# DDR4_SODIMM1.net
KiCad netlist of a schematic drawn in Altium Designer
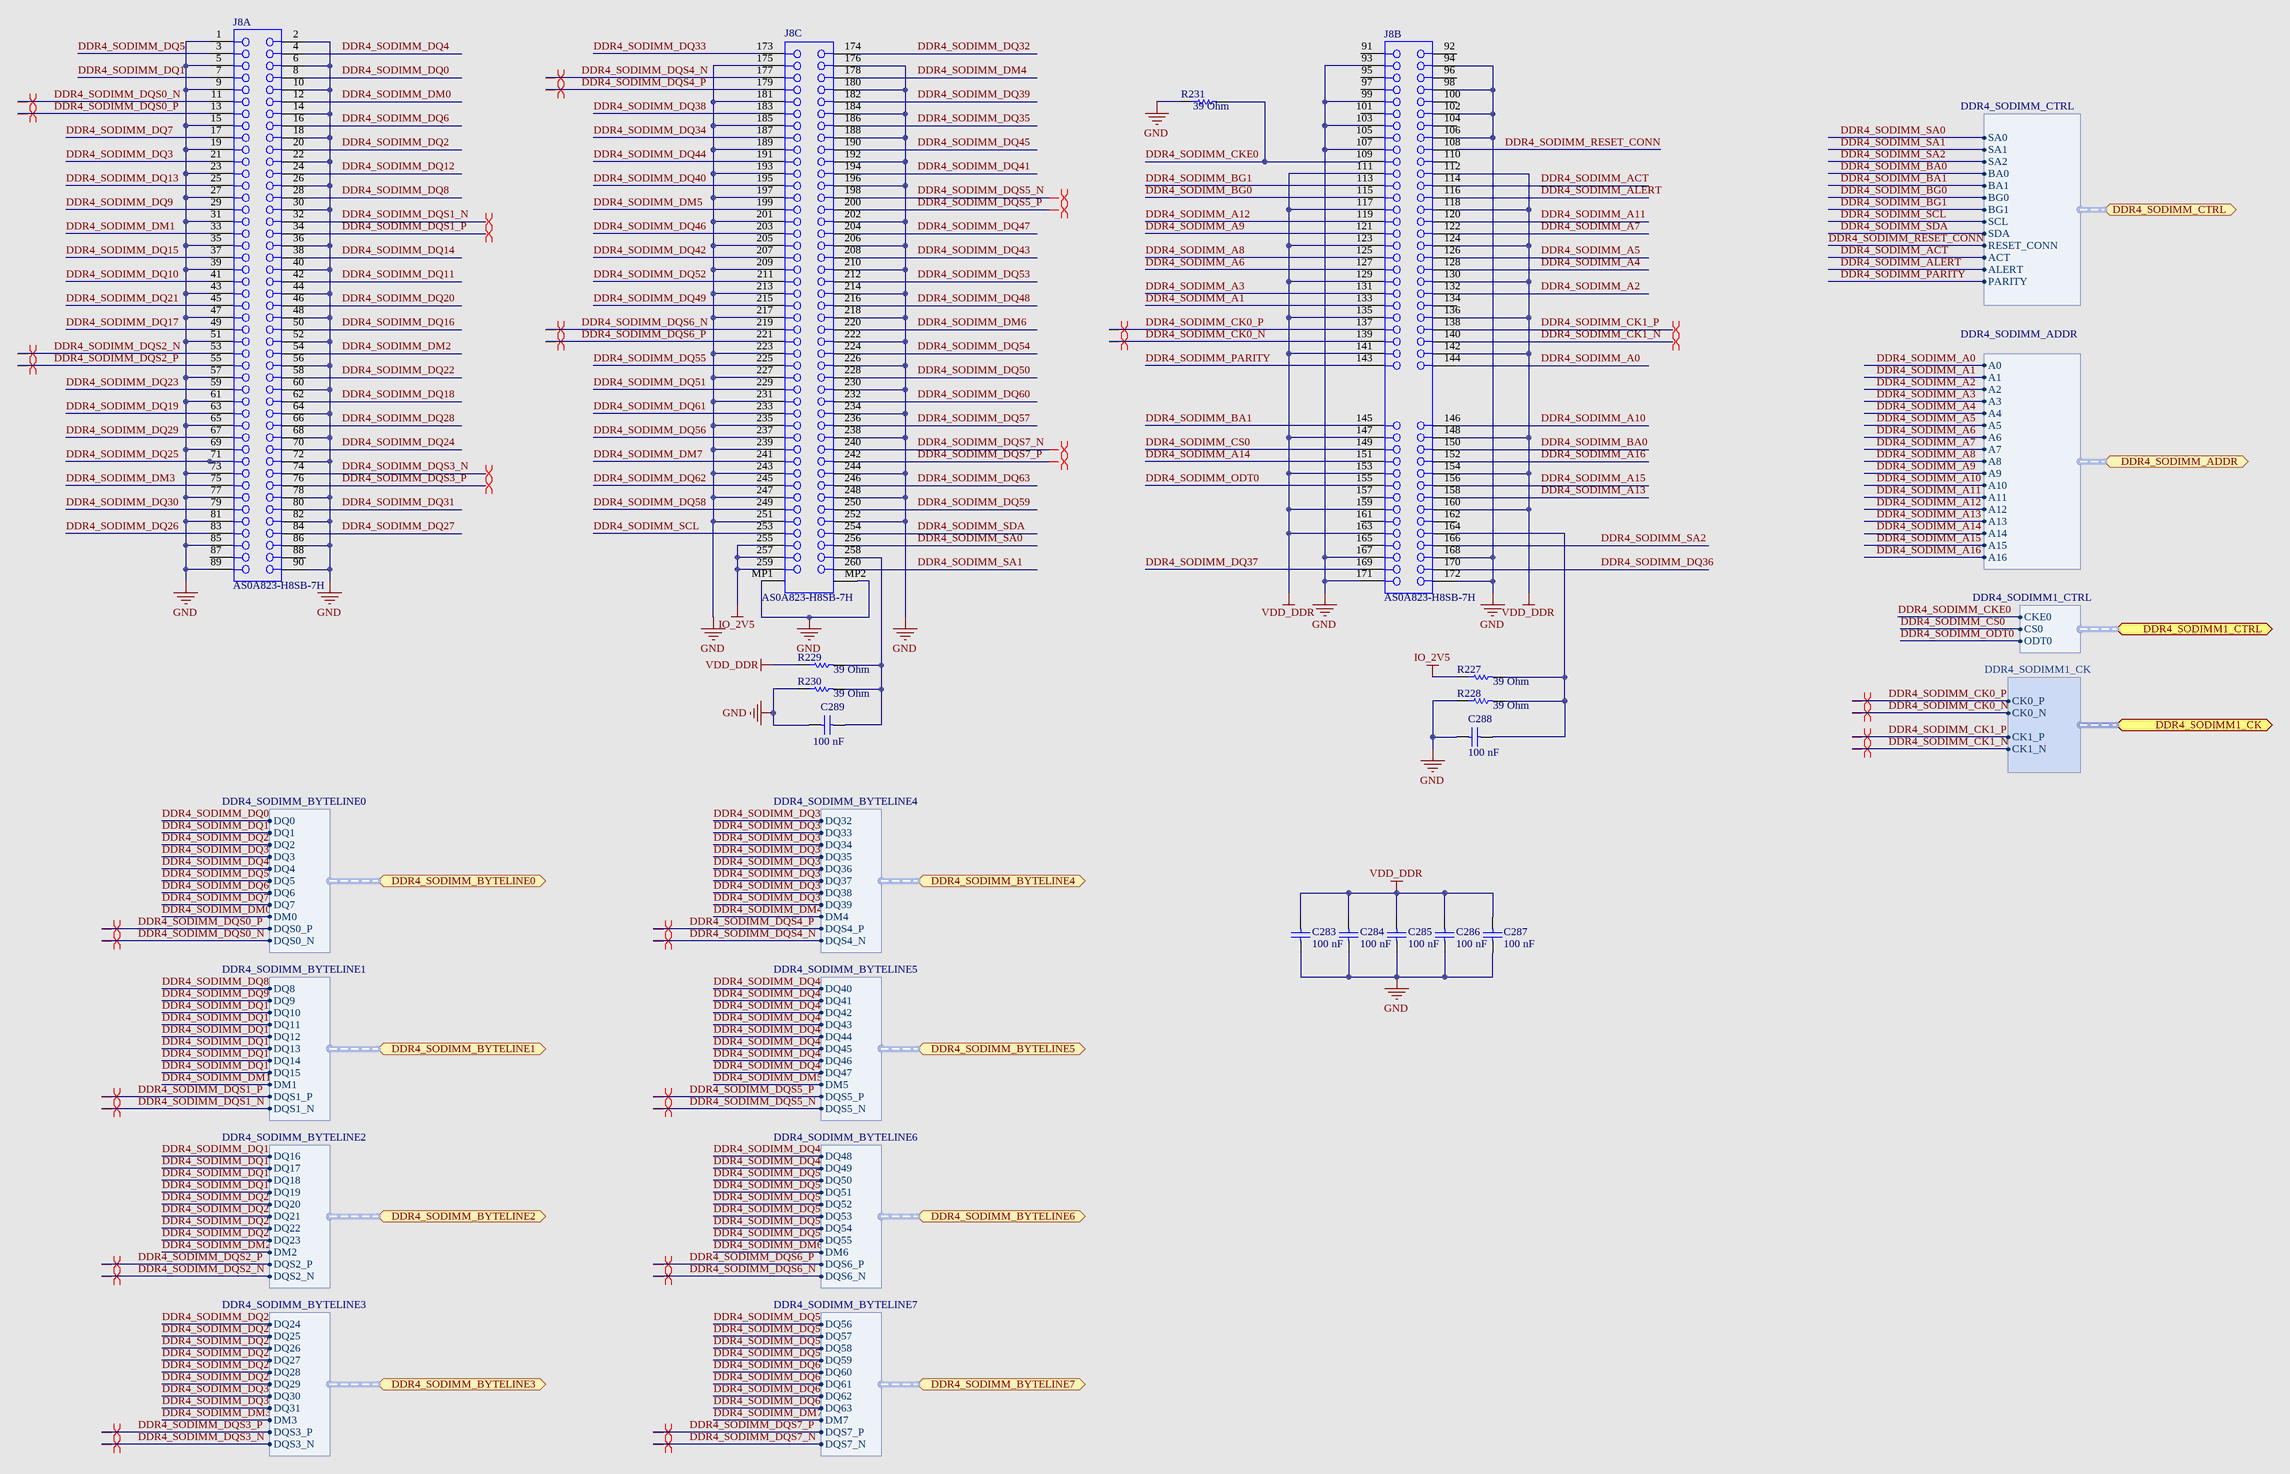
[diagram p0: DDR4_SODIMM1.SchDoc]

(export (version "E")
  (design (tool "Eeschema 10.0.6"))
  (components
    (comp (ref "C283")
      (value "C1005X7R1E104M")
      (footprint "CAPC1005X55X10LL05")
      (description "Chip Capacitor, 0.1 uF, +/- 20%, 25 V, -55 to 125 degC, 0402 (1005 Metric), RoHS, Tape and Reel")
      (fields (field (name "TOLERANCE") "20%") (field (name "CAPACITANCE") "100 nF"))
      (libsource (lib "Altium Content Vault") (part "CAP-NP-2"))
    )
    (comp (ref "C284")
      (value "C1005X7R1E104M")
      (footprint "CAPC1005X55X10LL05")
      (description "Chip Capacitor, 0.1 uF, +/- 20%, 25 V, -55 to 125 degC, 0402 (1005 Metric), RoHS, Tape and Reel")
      (fields (field (name "TOLERANCE") "20%") (field (name "CAPACITANCE") "100 nF"))
      (libsource (lib "Altium Content Vault") (part "CAP-NP-2"))
    )
    (comp (ref "C285")
      (value "C1005X7R1E104M")
      (footprint "CAPC1005X55X10LL05")
      (description "Chip Capacitor, 0.1 uF, +/- 20%, 25 V, -55 to 125 degC, 0402 (1005 Metric), RoHS, Tape and Reel")
      (fields (field (name "TOLERANCE") "20%") (field (name "CAPACITANCE") "100 nF"))
      (libsource (lib "Altium Content Vault") (part "CAP-NP-2"))
    )
    (comp (ref "C286")
      (value "C1005X7R1E104M")
      (footprint "CAPC1005X55X10LL05")
      (description "Chip Capacitor, 0.1 uF, +/- 20%, 25 V, -55 to 125 degC, 0402 (1005 Metric), RoHS, Tape and Reel")
      (fields (field (name "TOLERANCE") "20%") (field (name "CAPACITANCE") "100 nF"))
      (libsource (lib "Altium Content Vault") (part "CAP-NP-2"))
    )
    (comp (ref "C287")
      (value "C1005X7R1E104M")
      (footprint "CAPC1005X55X10LL05")
      (description "Chip Capacitor, 0.1 uF, +/- 20%, 25 V, -55 to 125 degC, 0402 (1005 Metric), RoHS, Tape and Reel")
      (fields (field (name "TOLERANCE") "20%") (field (name "CAPACITANCE") "100 nF"))
      (libsource (lib "Altium Content Vault") (part "CAP-NP-2"))
    )
    (comp (ref "C288")
      (value "C1005X7R1E104M")
      (footprint "CAPC1005X55X10LL05")
      (description "Chip Capacitor, 0.1 uF, +/- 20%, 25 V, -55 to 125 degC, 0402 (1005 Metric), RoHS, Tape and Reel")
      (fields (field (name "TOLERANCE") "20%") (field (name "CAPACITANCE") "100 nF"))
      (libsource (lib "Altium Content Vault") (part "CAP-NP-2"))
    )
    (comp (ref "C289")
      (value "C1005X7R1E104M")
      (footprint "CAPC1005X55X10LL05")
      (description "Chip Capacitor, 0.1 uF, +/- 20%, 25 V, -55 to 125 degC, 0402 (1005 Metric), RoHS, Tape and Reel")
      (fields (field (name "TOLERANCE") "20%") (field (name "CAPACITANCE") "100 nF"))
      (libsource (lib "Altium Content Vault") (part "CAP-NP-2"))
    )
    (comp (ref "J8")
      (value "AS0A823-H8SB-7H")
      (footprint "FOXC-AS0A823-H8SB-7H_V")
      (libsource (lib "Altium Content Vault") (part "CN-2S-2F-R260"))
    )
    (comp (ref "R227")
      (value "RC0402JR-0739RL")
      (footprint "RESC1005X40X25NL5T10")
      (description "Chip Resistor, 39 Ohm, +/- 5%, 0.063 W, -55 to 155 degC, 0402 (1005 Metric), RoHS, Tape and Reel")
      (fields (field (name "TOLERANCE") "5%") (field (name "RESISTANCE") "39 Ohm"))
      (libsource (lib "Altium Content Vault") (part "CMP-2002-07994-2"))
    )
    (comp (ref "R228")
      (value "RC0402JR-0739RL")
      (footprint "RESC1005X40X25NL5T10")
      (description "Chip Resistor, 39 Ohm, +/- 5%, 0.063 W, -55 to 155 degC, 0402 (1005 Metric), RoHS, Tape and Reel")
      (fields (field (name "TOLERANCE") "5%") (field (name "RESISTANCE") "39 Ohm"))
      (libsource (lib "Altium Content Vault") (part "CMP-2002-07994-2"))
    )
    (comp (ref "R229")
      (value "RC0402JR-0739RL")
      (footprint "RESC1005X40X25NL5T10")
      (description "Chip Resistor, 39 Ohm, +/- 5%, 0.063 W, -55 to 155 degC, 0402 (1005 Metric), RoHS, Tape and Reel")
      (fields (field (name "TOLERANCE") "5%") (field (name "RESISTANCE") "39 Ohm"))
      (libsource (lib "Altium Content Vault") (part "CMP-2002-07994-2"))
    )
    (comp (ref "R230")
      (value "RC0402JR-0739RL")
      (footprint "RESC1005X40X25NL5T10")
      (description "Chip Resistor, 39 Ohm, +/- 5%, 0.063 W, -55 to 155 degC, 0402 (1005 Metric), RoHS, Tape and Reel")
      (fields (field (name "TOLERANCE") "5%") (field (name "RESISTANCE") "39 Ohm"))
      (libsource (lib "Altium Content Vault") (part "CMP-2002-07994-2"))
    )
    (comp (ref "R231")
      (value "RC0402JR-0739RL")
      (footprint "RESC1005X40X25NL5T10")
      (description "Chip Resistor, 39 Ohm, +/- 5%, 0.063 W, -55 to 155 degC, 0402 (1005 Metric), RoHS, Tape and Reel")
      (fields (field (name "TOLERANCE") "5%") (field (name "RESISTANCE") "39 Ohm"))
      (libsource (lib "Altium Content Vault") (part "CMP-2002-07994-2"))
    )
  )
  (nets
    (net (code "13") (name "/DDR4_SODIMM_A0") (class "Default")
      (node (ref "J8") (pin "144") (pinfunction "144_144") (pintype "passive"))
    )
    (net (code "14") (name "/DDR4_SODIMM_A1") (class "Default")
      (node (ref "J8") (pin "133") (pinfunction "133_133") (pintype "passive"))
    )
    (net (code "15") (name "/DDR4_SODIMM_A2") (class "Default")
      (node (ref "J8") (pin "132") (pinfunction "132_132") (pintype "passive"))
    )
    (net (code "16") (name "/DDR4_SODIMM_A3") (class "Default")
      (node (ref "J8") (pin "131") (pinfunction "131_131") (pintype "passive"))
    )
    (net (code "17") (name "/DDR4_SODIMM_A4") (class "Default")
      (node (ref "J8") (pin "128") (pinfunction "128_128") (pintype "passive"))
    )
    (net (code "18") (name "/DDR4_SODIMM_A5") (class "Default")
      (node (ref "J8") (pin "126") (pinfunction "126_126") (pintype "passive"))
    )
    (net (code "19") (name "/DDR4_SODIMM_A6") (class "Default")
      (node (ref "J8") (pin "127") (pinfunction "127_127") (pintype "passive"))
    )
    (net (code "20") (name "/DDR4_SODIMM_A7") (class "Default")
      (node (ref "J8") (pin "122") (pinfunction "122_122") (pintype "passive"))
    )
    (net (code "21") (name "/DDR4_SODIMM_A8") (class "Default")
      (node (ref "J8") (pin "125") (pinfunction "125_125") (pintype "passive"))
    )
    (net (code "22") (name "/DDR4_SODIMM_A9") (class "Default")
      (node (ref "J8") (pin "121") (pinfunction "121_121") (pintype "passive"))
    )
    (net (code "23") (name "/DDR4_SODIMM_A10") (class "Default")
      (node (ref "J8") (pin "146") (pinfunction "146_146") (pintype "passive"))
    )
    (net (code "24") (name "/DDR4_SODIMM_A11") (class "Default")
      (node (ref "J8") (pin "120") (pinfunction "120_120") (pintype "passive"))
    )
    (net (code "25") (name "/DDR4_SODIMM_A12") (class "Default")
      (node (ref "J8") (pin "119") (pinfunction "119_119") (pintype "passive"))
    )
    (net (code "26") (name "/DDR4_SODIMM_A13") (class "Default")
      (node (ref "J8") (pin "158") (pinfunction "158_158") (pintype "passive"))
    )
    (net (code "27") (name "/DDR4_SODIMM_A14") (class "Default")
      (node (ref "J8") (pin "151") (pinfunction "151_151") (pintype "passive"))
    )
    (net (code "28") (name "/DDR4_SODIMM_A15") (class "Default")
      (node (ref "J8") (pin "156") (pinfunction "156_156") (pintype "passive"))
    )
    (net (code "29") (name "/DDR4_SODIMM_A16") (class "Default")
      (node (ref "J8") (pin "152") (pinfunction "152_152") (pintype "passive"))
    )
    (net (code "30") (name "/DDR4_SODIMM_ACT") (class "Default")
      (node (ref "J8") (pin "114") (pinfunction "114_114") (pintype "passive"))
    )
    (net (code "31") (name "/DDR4_SODIMM_ALERT") (class "Default")
      (node (ref "J8") (pin "116") (pinfunction "116_116") (pintype "passive"))
    )
    (net (code "32") (name "/DDR4_SODIMM_BA0") (class "Default")
      (node (ref "J8") (pin "150") (pinfunction "150_150") (pintype "passive"))
    )
    (net (code "33") (name "/DDR4_SODIMM_BA1") (class "Default")
      (node (ref "J8") (pin "145") (pinfunction "145_145") (pintype "passive"))
    )
    (net (code "34") (name "/DDR4_SODIMM_BG0") (class "Default")
      (node (ref "J8") (pin "115") (pinfunction "115_115") (pintype "passive"))
    )
    (net (code "35") (name "/DDR4_SODIMM_BG1") (class "Default")
      (node (ref "J8") (pin "113") (pinfunction "113_113") (pintype "passive"))
    )
    (net (code "36") (name "/DDR4_SODIMM_CK0_N") (class "Default")
      (node (ref "J8") (pin "139") (pinfunction "139_139") (pintype "passive"))
    )
    (net (code "37") (name "/DDR4_SODIMM_CK0_P") (class "Default")
      (node (ref "J8") (pin "137") (pinfunction "137_137") (pintype "passive"))
    )
    (net (code "38") (name "/DDR4_SODIMM_CK1_N") (class "Default")
      (node (ref "J8") (pin "140") (pinfunction "140_140") (pintype "passive"))
    )
    (net (code "39") (name "/DDR4_SODIMM_CK1_P") (class "Default")
      (node (ref "J8") (pin "138") (pinfunction "138_138") (pintype "passive"))
    )
    (net (code "40") (name "/DDR4_SODIMM_CKE0") (class "Default")
      (node (ref "J8") (pin "109") (pinfunction "109_109") (pintype "passive"))
      (node (ref "R231") (pin "2") (pinfunction "2_2") (pintype "passive"))
    )
    (net (code "41") (name "/DDR4_SODIMM_CS0") (class "Default")
      (node (ref "J8") (pin "149") (pinfunction "149_149") (pintype "passive"))
    )
    (net (code "42") (name "/DDR4_SODIMM_DM0") (class "Default")
      (node (ref "J8") (pin "12") (pinfunction "12_12") (pintype "passive"))
    )
    (net (code "43") (name "/DDR4_SODIMM_DM1") (class "Default")
      (node (ref "J8") (pin "33") (pinfunction "33_33") (pintype "passive"))
    )
    (net (code "44") (name "/DDR4_SODIMM_DM2") (class "Default")
      (node (ref "J8") (pin "54") (pinfunction "54_54") (pintype "passive"))
    )
    (net (code "45") (name "/DDR4_SODIMM_DM3") (class "Default")
      (node (ref "J8") (pin "75") (pinfunction "75_75") (pintype "passive"))
    )
    (net (code "46") (name "/DDR4_SODIMM_DM4") (class "Default")
      (node (ref "J8") (pin "178") (pinfunction "178_178") (pintype "passive"))
    )
    (net (code "47") (name "/DDR4_SODIMM_DM5") (class "Default")
      (node (ref "J8") (pin "199") (pinfunction "199_199") (pintype "passive"))
    )
    (net (code "48") (name "/DDR4_SODIMM_DM6") (class "Default")
      (node (ref "J8") (pin "220") (pinfunction "220_220") (pintype "passive"))
    )
    (net (code "49") (name "/DDR4_SODIMM_DM7") (class "Default")
      (node (ref "J8") (pin "241") (pinfunction "241_241") (pintype "passive"))
    )
    (net (code "50") (name "/DDR4_SODIMM_DQ0") (class "Default")
      (node (ref "J8") (pin "8") (pinfunction "8_8") (pintype "passive"))
    )
    (net (code "51") (name "/DDR4_SODIMM_DQ1") (class "Default")
      (node (ref "J8") (pin "7") (pinfunction "7_7") (pintype "passive"))
    )
    (net (code "52") (name "/DDR4_SODIMM_DQ2") (class "Default")
      (node (ref "J8") (pin "20") (pinfunction "20_20") (pintype "passive"))
    )
    (net (code "53") (name "/DDR4_SODIMM_DQ3") (class "Default")
      (node (ref "J8") (pin "21") (pinfunction "21_21") (pintype "passive"))
    )
    (net (code "54") (name "/DDR4_SODIMM_DQ4") (class "Default")
      (node (ref "J8") (pin "4") (pinfunction "4_4") (pintype "passive"))
    )
    (net (code "55") (name "/DDR4_SODIMM_DQ5") (class "Default")
      (node (ref "J8") (pin "3") (pinfunction "3_3") (pintype "passive"))
    )
    (net (code "56") (name "/DDR4_SODIMM_DQ6") (class "Default")
      (node (ref "J8") (pin "16") (pinfunction "16_16") (pintype "passive"))
    )
    (net (code "57") (name "/DDR4_SODIMM_DQ7") (class "Default")
      (node (ref "J8") (pin "17") (pinfunction "17_17") (pintype "passive"))
    )
    (net (code "58") (name "/DDR4_SODIMM_DQ8") (class "Default")
      (node (ref "J8") (pin "28") (pinfunction "28_28") (pintype "passive"))
    )
    (net (code "59") (name "/DDR4_SODIMM_DQ9") (class "Default")
      (node (ref "J8") (pin "29") (pinfunction "29_29") (pintype "passive"))
    )
    (net (code "60") (name "/DDR4_SODIMM_DQ10") (class "Default")
      (node (ref "J8") (pin "41") (pinfunction "41_41") (pintype "passive"))
    )
    (net (code "61") (name "/DDR4_SODIMM_DQ11") (class "Default")
      (node (ref "J8") (pin "42") (pinfunction "42_42") (pintype "passive"))
    )
    (net (code "62") (name "/DDR4_SODIMM_DQ12") (class "Default")
      (node (ref "J8") (pin "24") (pinfunction "24_24") (pintype "passive"))
    )
    (net (code "63") (name "/DDR4_SODIMM_DQ13") (class "Default")
      (node (ref "J8") (pin "25") (pinfunction "25_25") (pintype "passive"))
    )
    (net (code "64") (name "/DDR4_SODIMM_DQ14") (class "Default")
      (node (ref "J8") (pin "38") (pinfunction "38_38") (pintype "passive"))
    )
    (net (code "65") (name "/DDR4_SODIMM_DQ15") (class "Default")
      (node (ref "J8") (pin "37") (pinfunction "37_37") (pintype "passive"))
    )
    (net (code "66") (name "/DDR4_SODIMM_DQ16") (class "Default")
      (node (ref "J8") (pin "50") (pinfunction "50_50") (pintype "passive"))
    )
    (net (code "67") (name "/DDR4_SODIMM_DQ17") (class "Default")
      (node (ref "J8") (pin "49") (pinfunction "49_49") (pintype "passive"))
    )
    (net (code "68") (name "/DDR4_SODIMM_DQ18") (class "Default")
      (node (ref "J8") (pin "62") (pinfunction "62_62") (pintype "passive"))
    )
    (net (code "69") (name "/DDR4_SODIMM_DQ19") (class "Default")
      (node (ref "J8") (pin "63") (pinfunction "63_63") (pintype "passive"))
    )
    (net (code "70") (name "/DDR4_SODIMM_DQ20") (class "Default")
      (node (ref "J8") (pin "46") (pinfunction "46_46") (pintype "passive"))
    )
    (net (code "71") (name "/DDR4_SODIMM_DQ21") (class "Default")
      (node (ref "J8") (pin "45") (pinfunction "45_45") (pintype "passive"))
    )
    (net (code "72") (name "/DDR4_SODIMM_DQ22") (class "Default")
      (node (ref "J8") (pin "58") (pinfunction "58_58") (pintype "passive"))
    )
    (net (code "73") (name "/DDR4_SODIMM_DQ23") (class "Default")
      (node (ref "J8") (pin "59") (pinfunction "59_59") (pintype "passive"))
    )
    (net (code "74") (name "/DDR4_SODIMM_DQ24") (class "Default")
      (node (ref "J8") (pin "70") (pinfunction "70_70") (pintype "passive"))
    )
    (net (code "75") (name "/DDR4_SODIMM_DQ25") (class "Default")
      (node (ref "J8") (pin "71") (pinfunction "71_71") (pintype "passive"))
    )
    (net (code "76") (name "/DDR4_SODIMM_DQ26") (class "Default")
      (node (ref "J8") (pin "83") (pinfunction "83_83") (pintype "passive"))
    )
    (net (code "77") (name "/DDR4_SODIMM_DQ27") (class "Default")
      (node (ref "J8") (pin "84") (pinfunction "84_84") (pintype "passive"))
    )
    (net (code "78") (name "/DDR4_SODIMM_DQ28") (class "Default")
      (node (ref "J8") (pin "66") (pinfunction "66_66") (pintype "passive"))
    )
    (net (code "79") (name "/DDR4_SODIMM_DQ29") (class "Default")
      (node (ref "J8") (pin "67") (pinfunction "67_67") (pintype "passive"))
    )
    (net (code "80") (name "/DDR4_SODIMM_DQ30") (class "Default")
      (node (ref "J8") (pin "79") (pinfunction "79_79") (pintype "passive"))
    )
    (net (code "81") (name "/DDR4_SODIMM_DQ31") (class "Default")
      (node (ref "J8") (pin "80") (pinfunction "80_80") (pintype "passive"))
    )
    (net (code "82") (name "/DDR4_SODIMM_DQ32") (class "Default")
      (node (ref "J8") (pin "174") (pinfunction "174_174") (pintype "passive"))
    )
    (net (code "83") (name "/DDR4_SODIMM_DQ33") (class "Default")
      (node (ref "J8") (pin "173") (pinfunction "173_173") (pintype "passive"))
    )
    (net (code "84") (name "/DDR4_SODIMM_DQ34") (class "Default")
      (node (ref "J8") (pin "187") (pinfunction "187_187") (pintype "passive"))
    )
    (net (code "85") (name "/DDR4_SODIMM_DQ35") (class "Default")
      (node (ref "J8") (pin "186") (pinfunction "186_186") (pintype "passive"))
    )
    (net (code "86") (name "/DDR4_SODIMM_DQ36") (class "Default")
      (node (ref "J8") (pin "170") (pinfunction "170_170") (pintype "passive"))
    )
    (net (code "87") (name "/DDR4_SODIMM_DQ37") (class "Default")
      (node (ref "J8") (pin "169") (pinfunction "169_169") (pintype "passive"))
    )
    (net (code "88") (name "/DDR4_SODIMM_DQ38") (class "Default")
      (node (ref "J8") (pin "183") (pinfunction "183_183") (pintype "passive"))
    )
    (net (code "89") (name "/DDR4_SODIMM_DQ39") (class "Default")
      (node (ref "J8") (pin "182") (pinfunction "182_182") (pintype "passive"))
    )
    (net (code "90") (name "/DDR4_SODIMM_DQ40") (class "Default")
      (node (ref "J8") (pin "195") (pinfunction "195_195") (pintype "passive"))
    )
    (net (code "91") (name "/DDR4_SODIMM_DQ41") (class "Default")
      (node (ref "J8") (pin "194") (pinfunction "194_194") (pintype "passive"))
    )
    (net (code "92") (name "/DDR4_SODIMM_DQ42") (class "Default")
      (node (ref "J8") (pin "207") (pinfunction "207_207") (pintype "passive"))
    )
    (net (code "93") (name "/DDR4_SODIMM_DQ43") (class "Default")
      (node (ref "J8") (pin "208") (pinfunction "208_208") (pintype "passive"))
    )
    (net (code "94") (name "/DDR4_SODIMM_DQ44") (class "Default")
      (node (ref "J8") (pin "191") (pinfunction "191_191") (pintype "passive"))
    )
    (net (code "95") (name "/DDR4_SODIMM_DQ45") (class "Default")
      (node (ref "J8") (pin "190") (pinfunction "190_190") (pintype "passive"))
    )
    (net (code "96") (name "/DDR4_SODIMM_DQ46") (class "Default")
      (node (ref "J8") (pin "203") (pinfunction "203_203") (pintype "passive"))
    )
    (net (code "97") (name "/DDR4_SODIMM_DQ47") (class "Default")
      (node (ref "J8") (pin "204") (pinfunction "204_204") (pintype "passive"))
    )
    (net (code "98") (name "/DDR4_SODIMM_DQ48") (class "Default")
      (node (ref "J8") (pin "216") (pinfunction "216_216") (pintype "passive"))
    )
    (net (code "99") (name "/DDR4_SODIMM_DQ49") (class "Default")
      (node (ref "J8") (pin "215") (pinfunction "215_215") (pintype "passive"))
    )
    (net (code "100") (name "/DDR4_SODIMM_DQ50") (class "Default")
      (node (ref "J8") (pin "228") (pinfunction "228_228") (pintype "passive"))
    )
    (net (code "101") (name "/DDR4_SODIMM_DQ51") (class "Default")
      (node (ref "J8") (pin "229") (pinfunction "229_229") (pintype "passive"))
    )
    (net (code "102") (name "/DDR4_SODIMM_DQ52") (class "Default")
      (node (ref "J8") (pin "211") (pinfunction "211_211") (pintype "passive"))
    )
    (net (code "103") (name "/DDR4_SODIMM_DQ53") (class "Default")
      (node (ref "J8") (pin "212") (pinfunction "212_212") (pintype "passive"))
    )
    (net (code "104") (name "/DDR4_SODIMM_DQ54") (class "Default")
      (node (ref "J8") (pin "224") (pinfunction "224_224") (pintype "passive"))
    )
    (net (code "105") (name "/DDR4_SODIMM_DQ55") (class "Default")
      (node (ref "J8") (pin "225") (pinfunction "225_225") (pintype "passive"))
    )
    (net (code "106") (name "/DDR4_SODIMM_DQ56") (class "Default")
      (node (ref "J8") (pin "237") (pinfunction "237_237") (pintype "passive"))
    )
    (net (code "107") (name "/DDR4_SODIMM_DQ57") (class "Default")
      (node (ref "J8") (pin "236") (pinfunction "236_236") (pintype "passive"))
    )
    (net (code "108") (name "/DDR4_SODIMM_DQ58") (class "Default")
      (node (ref "J8") (pin "249") (pinfunction "249_249") (pintype "passive"))
    )
    (net (code "109") (name "/DDR4_SODIMM_DQ59") (class "Default")
      (node (ref "J8") (pin "250") (pinfunction "250_250") (pintype "passive"))
    )
    (net (code "110") (name "/DDR4_SODIMM_DQ60") (class "Default")
      (node (ref "J8") (pin "232") (pinfunction "232_232") (pintype "passive"))
    )
    (net (code "111") (name "/DDR4_SODIMM_DQ61") (class "Default")
      (node (ref "J8") (pin "233") (pinfunction "233_233") (pintype "passive"))
    )
    (net (code "112") (name "/DDR4_SODIMM_DQ62") (class "Default")
      (node (ref "J8") (pin "245") (pinfunction "245_245") (pintype "passive"))
    )
    (net (code "113") (name "/DDR4_SODIMM_DQ63") (class "Default")
      (node (ref "J8") (pin "246") (pinfunction "246_246") (pintype "passive"))
    )
    (net (code "114") (name "/DDR4_SODIMM_DQS0_N") (class "Default")
      (node (ref "J8") (pin "11") (pinfunction "11_11") (pintype "passive"))
    )
    (net (code "115") (name "/DDR4_SODIMM_DQS0_P") (class "Default")
      (node (ref "J8") (pin "13") (pinfunction "13_13") (pintype "passive"))
    )
    (net (code "116") (name "/DDR4_SODIMM_DQS1_N") (class "Default")
      (node (ref "J8") (pin "32") (pinfunction "32_32") (pintype "passive"))
    )
    (net (code "117") (name "/DDR4_SODIMM_DQS1_P") (class "Default")
      (node (ref "J8") (pin "34") (pinfunction "34_34") (pintype "passive"))
    )
    (net (code "118") (name "/DDR4_SODIMM_DQS2_N") (class "Default")
      (node (ref "J8") (pin "53") (pinfunction "53_53") (pintype "passive"))
    )
    (net (code "119") (name "/DDR4_SODIMM_DQS2_P") (class "Default")
      (node (ref "J8") (pin "55") (pinfunction "55_55") (pintype "passive"))
    )
    (net (code "120") (name "/DDR4_SODIMM_DQS3_N") (class "Default")
      (node (ref "J8") (pin "74") (pinfunction "74_74") (pintype "passive"))
    )
    (net (code "121") (name "/DDR4_SODIMM_DQS3_P") (class "Default")
      (node (ref "J8") (pin "76") (pinfunction "76_76") (pintype "passive"))
    )
    (net (code "122") (name "/DDR4_SODIMM_DQS4_N") (class "Default")
      (node (ref "J8") (pin "177") (pinfunction "177_177") (pintype "passive"))
    )
    (net (code "123") (name "/DDR4_SODIMM_DQS4_P") (class "Default")
      (node (ref "J8") (pin "179") (pinfunction "179_179") (pintype "passive"))
    )
    (net (code "124") (name "/DDR4_SODIMM_DQS5_N") (class "Default")
      (node (ref "J8") (pin "198") (pinfunction "198_198") (pintype "passive"))
    )
    (net (code "125") (name "/DDR4_SODIMM_DQS5_P") (class "Default")
      (node (ref "J8") (pin "200") (pinfunction "200_200") (pintype "passive"))
    )
    (net (code "126") (name "/DDR4_SODIMM_DQS6_N") (class "Default")
      (node (ref "J8") (pin "219") (pinfunction "219_219") (pintype "passive"))
    )
    (net (code "127") (name "/DDR4_SODIMM_DQS6_P") (class "Default")
      (node (ref "J8") (pin "221") (pinfunction "221_221") (pintype "passive"))
    )
    (net (code "128") (name "/DDR4_SODIMM_DQS7_N") (class "Default")
      (node (ref "J8") (pin "240") (pinfunction "240_240") (pintype "passive"))
    )
    (net (code "129") (name "/DDR4_SODIMM_DQS7_P") (class "Default")
      (node (ref "J8") (pin "242") (pinfunction "242_242") (pintype "passive"))
    )
    (net (code "130") (name "/DDR4_SODIMM_ODT0") (class "Default")
      (node (ref "J8") (pin "155") (pinfunction "155_155") (pintype "passive"))
    )
    (net (code "131") (name "/DDR4_SODIMM_PARITY") (class "Default")
      (node (ref "J8") (pin "143") (pinfunction "143_143") (pintype "passive"))
    )
    (net (code "132") (name "/DDR4_SODIMM_RESET_CONN") (class "Default")
      (node (ref "J8") (pin "108") (pinfunction "108_108") (pintype "passive"))
    )
    (net (code "133") (name "/DDR4_SODIMM_SA0") (class "Default")
      (node (ref "J8") (pin "256") (pinfunction "256_256") (pintype "passive"))
    )
    (net (code "134") (name "/DDR4_SODIMM_SA1") (class "Default")
      (node (ref "J8") (pin "260") (pinfunction "260_260") (pintype "passive"))
    )
    (net (code "135") (name "/DDR4_SODIMM_SA2") (class "Default")
      (node (ref "J8") (pin "166") (pinfunction "166_166") (pintype "passive"))
    )
    (net (code "136") (name "/DDR4_SODIMM_SCL") (class "Default")
      (node (ref "J8") (pin "253") (pinfunction "253_253") (pintype "passive"))
    )
    (net (code "137") (name "/DDR4_SODIMM_SDA") (class "Default")
      (node (ref "J8") (pin "254") (pinfunction "254_254") (pintype "passive"))
    )
    (net (code "150") (name "GND") (class "Default")
      (node (ref "C283") (pin "2") (pinfunction "2_2") (pintype "passive"))
      (node (ref "C284") (pin "2") (pinfunction "2_2") (pintype "passive"))
      (node (ref "C285") (pin "2") (pinfunction "2_2") (pintype "passive"))
      (node (ref "C286") (pin "2") (pinfunction "2_2") (pintype "passive"))
      (node (ref "C287") (pin "2") (pinfunction "2_2") (pintype "passive"))
      (node (ref "C288") (pin "1") (pinfunction "1_1") (pintype "passive"))
      (node (ref "C289") (pin "2") (pinfunction "2_2") (pintype "passive"))
      (node (ref "J8") (pin "1") (pinfunction "1_1") (pintype "passive"))
      (node (ref "J8") (pin "10") (pinfunction "10_10") (pintype "passive"))
      (node (ref "J8") (pin "102") (pinfunction "102_102") (pintype "passive"))
      (node (ref "J8") (pin "103") (pinfunction "103_103") (pintype "passive"))
      (node (ref "J8") (pin "106") (pinfunction "106_106") (pintype "passive"))
      (node (ref "J8") (pin "107") (pinfunction "107_107") (pintype "passive"))
      (node (ref "J8") (pin "14") (pinfunction "14_14") (pintype "passive"))
      (node (ref "J8") (pin "15") (pinfunction "15_15") (pintype "passive"))
      (node (ref "J8") (pin "167") (pinfunction "167_167") (pintype "passive"))
      (node (ref "J8") (pin "168") (pinfunction "168_168") (pintype "passive"))
      (node (ref "J8") (pin "171") (pinfunction "171_171") (pintype "passive"))
      (node (ref "J8") (pin "172") (pinfunction "172_172") (pintype "passive"))
      (node (ref "J8") (pin "175") (pinfunction "175_175") (pintype "passive"))
      (node (ref "J8") (pin "176") (pinfunction "176_176") (pintype "passive"))
      (node (ref "J8") (pin "18") (pinfunction "18_18") (pintype "passive"))
      (node (ref "J8") (pin "180") (pinfunction "180_180") (pintype "passive"))
      (node (ref "J8") (pin "181") (pinfunction "181_181") (pintype "passive"))
      (node (ref "J8") (pin "184") (pinfunction "184_184") (pintype "passive"))
      (node (ref "J8") (pin "185") (pinfunction "185_185") (pintype "passive"))
      (node (ref "J8") (pin "188") (pinfunction "188_188") (pintype "passive"))
      (node (ref "J8") (pin "189") (pinfunction "189_189") (pintype "passive"))
      (node (ref "J8") (pin "19") (pinfunction "19_19") (pintype "passive"))
      (node (ref "J8") (pin "192") (pinfunction "192_192") (pintype "passive"))
      (node (ref "J8") (pin "193") (pinfunction "193_193") (pintype "passive"))
      (node (ref "J8") (pin "196") (pinfunction "196_196") (pintype "passive"))
      (node (ref "J8") (pin "197") (pinfunction "197_197") (pintype "passive"))
      (node (ref "J8") (pin "2") (pinfunction "2_2") (pintype "passive"))
      (node (ref "J8") (pin "201") (pinfunction "201_201") (pintype "passive"))
      (node (ref "J8") (pin "202") (pinfunction "202_202") (pintype "passive"))
      (node (ref "J8") (pin "205") (pinfunction "205_205") (pintype "passive"))
      (node (ref "J8") (pin "206") (pinfunction "206_206") (pintype "passive"))
      (node (ref "J8") (pin "209") (pinfunction "209_209") (pintype "passive"))
      (node (ref "J8") (pin "210") (pinfunction "210_210") (pintype "passive"))
      (node (ref "J8") (pin "213") (pinfunction "213_213") (pintype "passive"))
      (node (ref "J8") (pin "214") (pinfunction "214_214") (pintype "passive"))
      (node (ref "J8") (pin "217") (pinfunction "217_217") (pintype "passive"))
      (node (ref "J8") (pin "218") (pinfunction "218_218") (pintype "passive"))
      (node (ref "J8") (pin "22") (pinfunction "22_22") (pintype "passive"))
      (node (ref "J8") (pin "222") (pinfunction "222_222") (pintype "passive"))
      (node (ref "J8") (pin "223") (pinfunction "223_223") (pintype "passive"))
      (node (ref "J8") (pin "226") (pinfunction "226_226") (pintype "passive"))
      (node (ref "J8") (pin "227") (pinfunction "227_227") (pintype "passive"))
      (node (ref "J8") (pin "23") (pinfunction "23_23") (pintype "passive"))
      (node (ref "J8") (pin "230") (pinfunction "230_230") (pintype "passive"))
      (node (ref "J8") (pin "231") (pinfunction "231_231") (pintype "passive"))
      (node (ref "J8") (pin "234") (pinfunction "234_234") (pintype "passive"))
      (node (ref "J8") (pin "235") (pinfunction "235_235") (pintype "passive"))
      (node (ref "J8") (pin "238") (pinfunction "238_238") (pintype "passive"))
      (node (ref "J8") (pin "239") (pinfunction "239_239") (pintype "passive"))
      (node (ref "J8") (pin "243") (pinfunction "243_243") (pintype "passive"))
      (node (ref "J8") (pin "244") (pinfunction "244_244") (pintype "passive"))
      (node (ref "J8") (pin "247") (pinfunction "247_247") (pintype "passive"))
      (node (ref "J8") (pin "248") (pinfunction "248_248") (pintype "passive"))
      (node (ref "J8") (pin "251") (pinfunction "251_251") (pintype "passive"))
      (node (ref "J8") (pin "252") (pinfunction "252_252") (pintype "passive"))
      (node (ref "J8") (pin "26") (pinfunction "26_26") (pintype "passive"))
      (node (ref "J8") (pin "27") (pinfunction "27_27") (pintype "passive"))
      (node (ref "J8") (pin "30") (pinfunction "30_30") (pintype "passive"))
      (node (ref "J8") (pin "31") (pinfunction "31_31") (pintype "passive"))
      (node (ref "J8") (pin "35") (pinfunction "35_35") (pintype "passive"))
      (node (ref "J8") (pin "36") (pinfunction "36_36") (pintype "passive"))
      (node (ref "J8") (pin "39") (pinfunction "39_39") (pintype "passive"))
      (node (ref "J8") (pin "40") (pinfunction "40_40") (pintype "passive"))
      (node (ref "J8") (pin "43") (pinfunction "43_43") (pintype "passive"))
      (node (ref "J8") (pin "44") (pinfunction "44_44") (pintype "passive"))
      (node (ref "J8") (pin "47") (pinfunction "47_47") (pintype "passive"))
      (node (ref "J8") (pin "48") (pinfunction "48_48") (pintype "passive"))
      (node (ref "J8") (pin "5") (pinfunction "5_5") (pintype "passive"))
      (node (ref "J8") (pin "51") (pinfunction "51_51") (pintype "passive"))
      (node (ref "J8") (pin "52") (pinfunction "52_52") (pintype "passive"))
      (node (ref "J8") (pin "56") (pinfunction "56_56") (pintype "passive"))
      (node (ref "J8") (pin "57") (pinfunction "57_57") (pintype "passive"))
      (node (ref "J8") (pin "6") (pinfunction "6_6") (pintype "passive"))
      (node (ref "J8") (pin "60") (pinfunction "60_60") (pintype "passive"))
      (node (ref "J8") (pin "61") (pinfunction "61_61") (pintype "passive"))
      (node (ref "J8") (pin "64") (pinfunction "64_64") (pintype "passive"))
      (node (ref "J8") (pin "65") (pinfunction "65_65") (pintype "passive"))
      (node (ref "J8") (pin "68") (pinfunction "68_68") (pintype "passive"))
      (node (ref "J8") (pin "69") (pinfunction "69_69") (pintype "passive"))
      (node (ref "J8") (pin "72") (pinfunction "72_72") (pintype "passive"))
      (node (ref "J8") (pin "73") (pinfunction "73_73") (pintype "passive"))
      (node (ref "J8") (pin "77") (pinfunction "77_77") (pintype "passive"))
      (node (ref "J8") (pin "78") (pinfunction "78_78") (pintype "passive"))
      (node (ref "J8") (pin "81") (pinfunction "81_81") (pintype "passive"))
      (node (ref "J8") (pin "82") (pinfunction "82_82") (pintype "passive"))
      (node (ref "J8") (pin "85") (pinfunction "85_85") (pintype "passive"))
      (node (ref "J8") (pin "86") (pinfunction "86_86") (pintype "passive"))
      (node (ref "J8") (pin "89") (pinfunction "89_89") (pintype "passive"))
      (node (ref "J8") (pin "9") (pinfunction "9_9") (pintype "passive"))
      (node (ref "J8") (pin "90") (pinfunction "90_90") (pintype "passive"))
      (node (ref "J8") (pin "93") (pinfunction "93_93") (pintype "passive"))
      (node (ref "J8") (pin "94") (pinfunction "94_94") (pintype "passive"))
      (node (ref "J8") (pin "98") (pinfunction "98_98") (pintype "passive"))
      (node (ref "J8") (pin "99") (pinfunction "99_99") (pintype "passive"))
      (node (ref "J8") (pin "MP1") (pinfunction "MP1_MP1") (pintype "passive"))
      (node (ref "J8") (pin "MP2") (pinfunction "MP2_MP2") (pintype "passive"))
      (node (ref "R228") (pin "1") (pinfunction "1_1") (pintype "passive"))
      (node (ref "R230") (pin "1") (pinfunction "1_1") (pintype "passive"))
      (node (ref "R231") (pin "1") (pinfunction "1_1") (pintype "passive"))
    )
    (net (code "151") (name "IO_2V5") (class "Default")
      (node (ref "J8") (pin "255") (pinfunction "255_255") (pintype "passive"))
      (node (ref "J8") (pin "257") (pinfunction "257_257") (pintype "passive"))
      (node (ref "J8") (pin "259") (pinfunction "259_259") (pintype "passive"))
      (node (ref "R227") (pin "1") (pinfunction "1_1") (pintype "passive"))
    )
    (net (code "152") (name "Net-(C288-Pad2)") (class "Default")
      (node (ref "C288") (pin "2") (pinfunction "2_2") (pintype "passive"))
      (node (ref "J8") (pin "164") (pinfunction "164_164") (pintype "passive"))
      (node (ref "R227") (pin "2") (pinfunction "2_2") (pintype "passive"))
      (node (ref "R228") (pin "2") (pinfunction "2_2") (pintype "passive"))
    )
    (net (code "153") (name "Net-(C289-Pad1)") (class "Default")
      (node (ref "C289") (pin "1") (pinfunction "1_1") (pintype "passive"))
      (node (ref "J8") (pin "258") (pinfunction "258_258") (pintype "passive"))
      (node (ref "R229") (pin "2") (pinfunction "2_2") (pintype "passive"))
      (node (ref "R230") (pin "2") (pinfunction "2_2") (pintype "passive"))
    )
    (net (code "154") (name "VDD_DDR") (class "Default")
      (node (ref "C283") (pin "1") (pinfunction "1_1") (pintype "passive"))
      (node (ref "C284") (pin "1") (pinfunction "1_1") (pintype "passive"))
      (node (ref "C285") (pin "1") (pinfunction "1_1") (pintype "passive"))
      (node (ref "C286") (pin "1") (pinfunction "1_1") (pintype "passive"))
      (node (ref "C287") (pin "1") (pinfunction "1_1") (pintype "passive"))
      (node (ref "J8") (pin "111") (pinfunction "111_111") (pintype "passive"))
      (node (ref "J8") (pin "112") (pinfunction "112_112") (pintype "passive"))
      (node (ref "J8") (pin "117") (pinfunction "117_117") (pintype "passive"))
      (node (ref "J8") (pin "118") (pinfunction "118_118") (pintype "passive"))
      (node (ref "J8") (pin "123") (pinfunction "123_123") (pintype "passive"))
      (node (ref "J8") (pin "124") (pinfunction "124_124") (pintype "passive"))
      (node (ref "J8") (pin "129") (pinfunction "129_129") (pintype "passive"))
      (node (ref "J8") (pin "130") (pinfunction "130_130") (pintype "passive"))
      (node (ref "J8") (pin "135") (pinfunction "135_135") (pintype "passive"))
      (node (ref "J8") (pin "136") (pinfunction "136_136") (pintype "passive"))
      (node (ref "J8") (pin "141") (pinfunction "141_141") (pintype "passive"))
      (node (ref "J8") (pin "142") (pinfunction "142_142") (pintype "passive"))
      (node (ref "J8") (pin "147") (pinfunction "147_147") (pintype "passive"))
      (node (ref "J8") (pin "148") (pinfunction "148_148") (pintype "passive"))
      (node (ref "J8") (pin "153") (pinfunction "153_153") (pintype "passive"))
      (node (ref "J8") (pin "154") (pinfunction "154_154") (pintype "passive"))
      (node (ref "J8") (pin "159") (pinfunction "159_159") (pintype "passive"))
      (node (ref "J8") (pin "160") (pinfunction "160_160") (pintype "passive"))
      (node (ref "J8") (pin "163") (pinfunction "163_163") (pintype "passive"))
      (node (ref "R229") (pin "1") (pinfunction "1_1") (pintype "passive"))
    )
    (net (code "155") (name "unconnected-(J8-Pad87)") (class "Default")
      (node (ref "J8") (pin "87") (pinfunction "87_87") (pintype "passive"))
    )
    (net (code "156") (name "unconnected-(J8-Pad88)") (class "Default")
      (node (ref "J8") (pin "88") (pinfunction "88_88") (pintype "passive"))
    )
    (net (code "157") (name "unconnected-(J8-Pad91)") (class "Default")
      (node (ref "J8") (pin "91") (pinfunction "91_91") (pintype "passive"))
    )
    (net (code "158") (name "unconnected-(J8-Pad92)") (class "Default")
      (node (ref "J8") (pin "92") (pinfunction "92_92") (pintype "passive"))
    )
    (net (code "159") (name "unconnected-(J8-Pad95)") (class "Default")
      (node (ref "J8") (pin "95") (pinfunction "95_95") (pintype "passive"))
    )
    (net (code "160") (name "unconnected-(J8-Pad96)") (class "Default")
      (node (ref "J8") (pin "96") (pinfunction "96_96") (pintype "passive"))
    )
    (net (code "161") (name "unconnected-(J8-Pad97)") (class "Default")
      (node (ref "J8") (pin "97") (pinfunction "97_97") (pintype "passive"))
    )
    (net (code "162") (name "unconnected-(J8-Pad100)") (class "Default")
      (node (ref "J8") (pin "100") (pinfunction "100_100") (pintype "passive"))
    )
    (net (code "163") (name "unconnected-(J8-Pad101)") (class "Default")
      (node (ref "J8") (pin "101") (pinfunction "101_101") (pintype "passive"))
    )
    (net (code "164") (name "unconnected-(J8-Pad104)") (class "Default")
      (node (ref "J8") (pin "104") (pinfunction "104_104") (pintype "passive"))
    )
    (net (code "165") (name "unconnected-(J8-Pad105)") (class "Default")
      (node (ref "J8") (pin "105") (pinfunction "105_105") (pintype "passive"))
    )
    (net (code "166") (name "unconnected-(J8-Pad110)") (class "Default")
      (node (ref "J8") (pin "110") (pinfunction "110_110") (pintype "passive"))
    )
    (net (code "167") (name "unconnected-(J8-Pad134)") (class "Default")
      (node (ref "J8") (pin "134") (pinfunction "134_134") (pintype "passive"))
    )
    (net (code "168") (name "unconnected-(J8-Pad157)") (class "Default")
      (node (ref "J8") (pin "157") (pinfunction "157_157") (pintype "passive"))
    )
    (net (code "169") (name "unconnected-(J8-Pad161)") (class "Default")
      (node (ref "J8") (pin "161") (pinfunction "161_161") (pintype "passive"))
    )
    (net (code "170") (name "unconnected-(J8-Pad162)") (class "Default")
      (node (ref "J8") (pin "162") (pinfunction "162_162") (pintype "passive"))
    )
    (net (code "171") (name "unconnected-(J8-Pad165)") (class "Default")
      (node (ref "J8") (pin "165") (pinfunction "165_165") (pintype "passive"))
    )
  )
)
